# pc_kalam_gpio_cap.net
KiCad netlist of a schematic drawn in EAGLE
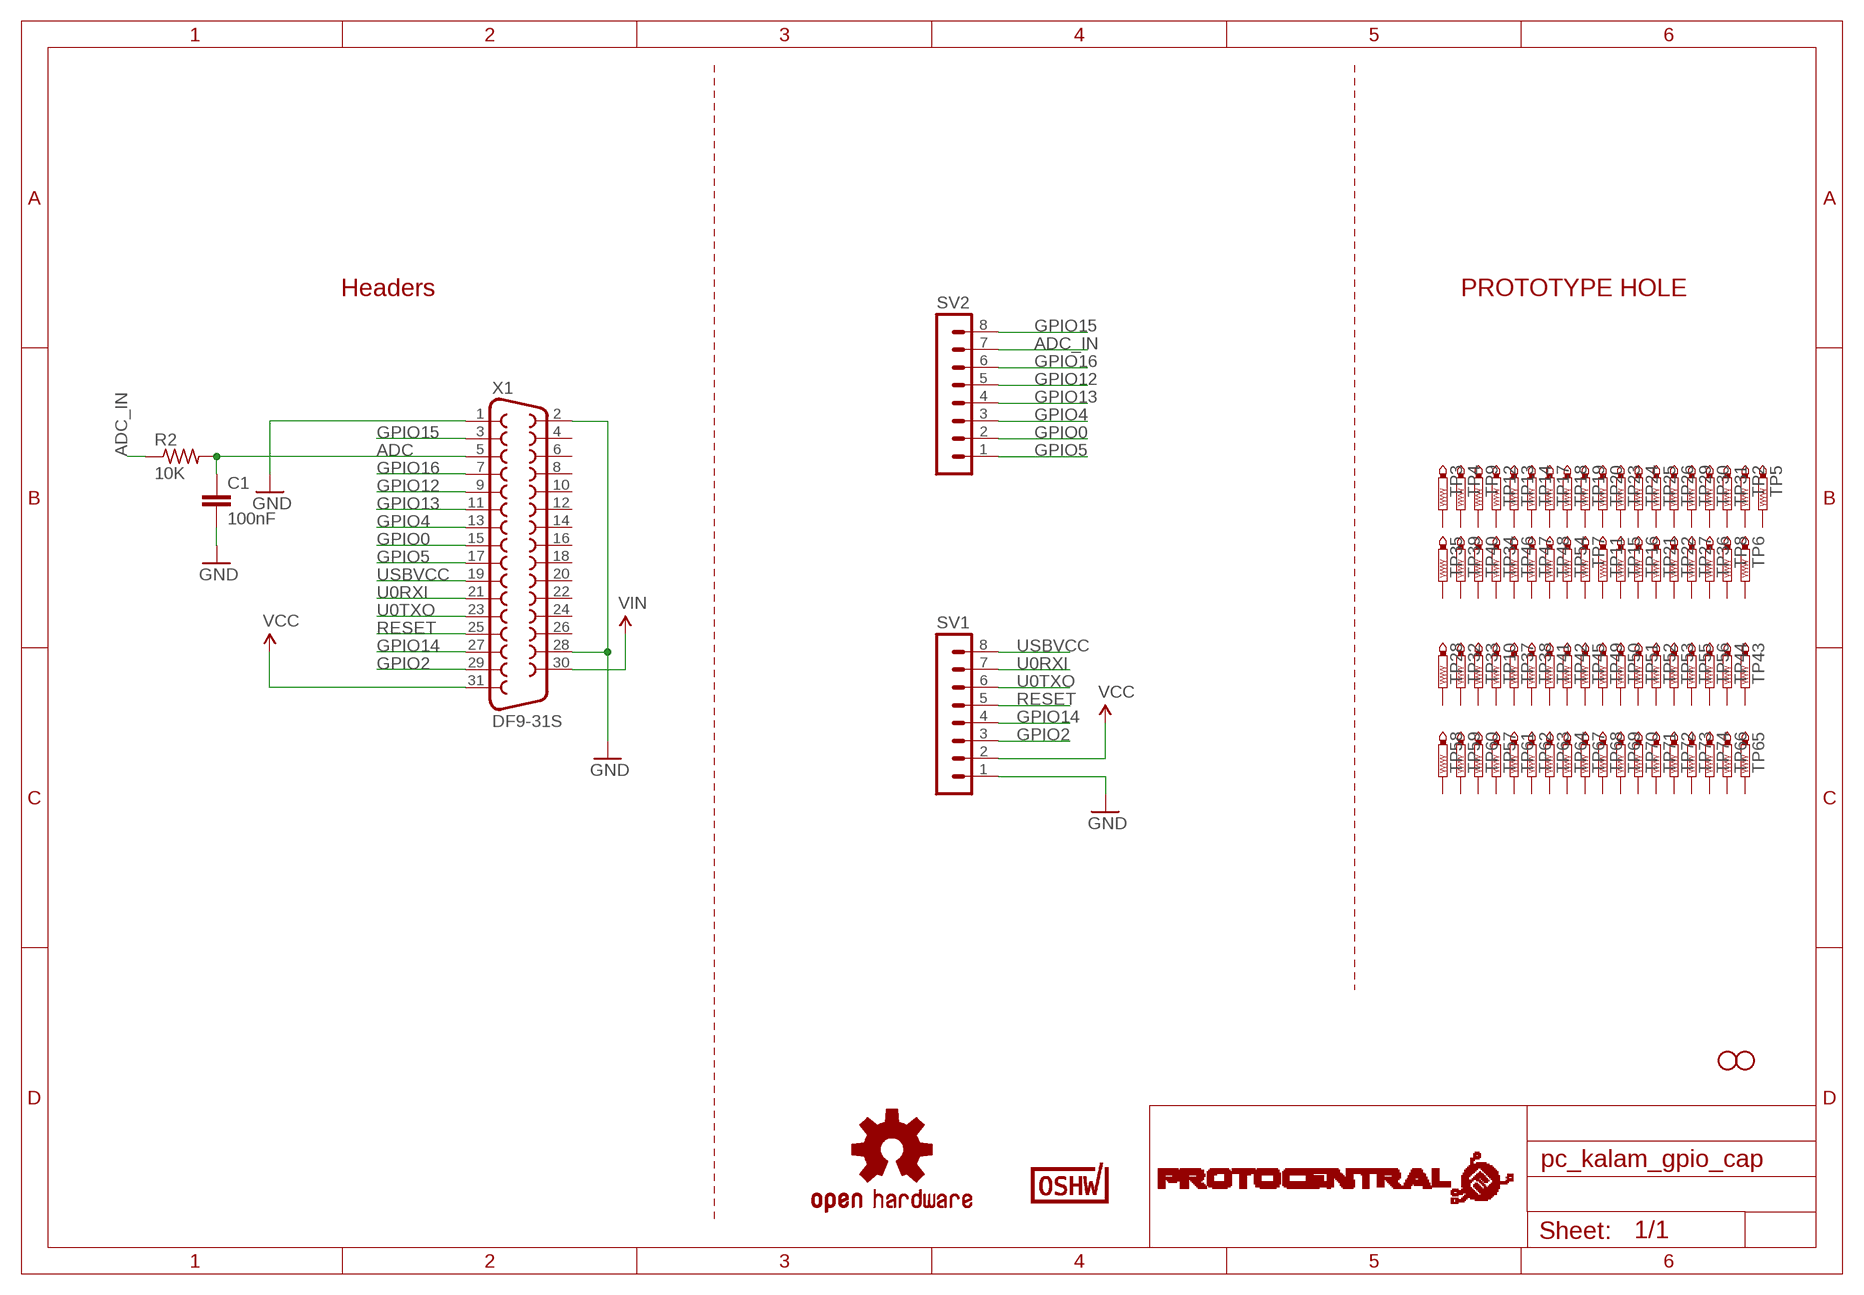
[diagram p0: schematic, sheet 1]

(export (version "E")
  (design (tool "Eeschema 10.0.6"))
  (components
    (comp (ref "C1")
      (value "100nF")
      (footprint "eagle-import:C0805")
      (libsource (lib "eagle-import") (part "C-EUC0805"))
    )
    (comp (ref "R2")
      (value "10K")
      (footprint "eagle-import:R0805")
      (libsource (lib "eagle-import") (part "R-US_R0805"))
    )
    (comp (ref "STANDOFF7")
      (value "STAND-OFF")
      (footprint "eagle-import:STAND-OFF")
      (libsource (lib "eagle-import") (part "STAND-OFF"))
    )
    (comp (ref "STANDOFF8")
      (value "STAND-OFF")
      (footprint "eagle-import:STAND-OFF")
      (libsource (lib "eagle-import") (part "STAND-OFF"))
    )
    (comp (ref "SV1")
      (value "MA08-1")
      (footprint "eagle-import:MA08-1")
      (libsource (lib "eagle-import") (part "MA08-1"))
    )
    (comp (ref "SV2")
      (value "MA08-1")
      (footprint "eagle-import:MA08-1")
      (libsource (lib "eagle-import") (part "MA08-1"))
    )
    (comp (ref "TP2")
      (value "PTR1PAD1-13")
      (footprint "eagle-import:P1-13")
      (libsource (lib "eagle-import") (part "PTR1PAD1-13"))
    )
    (comp (ref "TP3")
      (value "PTR1PAD1-13")
      (footprint "eagle-import:P1-13")
      (libsource (lib "eagle-import") (part "PTR1PAD1-13"))
    )
    (comp (ref "TP4")
      (value "PTR1PAD1-13")
      (footprint "eagle-import:P1-13")
      (libsource (lib "eagle-import") (part "PTR1PAD1-13"))
    )
    (comp (ref "TP5")
      (value "PTR1PAD1-13")
      (footprint "eagle-import:P1-13")
      (libsource (lib "eagle-import") (part "PTR1PAD1-13"))
    )
    (comp (ref "TP6")
      (value "PTR1PAD1-13")
      (footprint "eagle-import:P1-13")
      (libsource (lib "eagle-import") (part "PTR1PAD1-13"))
    )
    (comp (ref "TP7")
      (value "PTR1PAD1-13")
      (footprint "eagle-import:P1-13")
      (libsource (lib "eagle-import") (part "PTR1PAD1-13"))
    )
    (comp (ref "TP8")
      (value "PTR1PAD1-13")
      (footprint "eagle-import:P1-13")
      (libsource (lib "eagle-import") (part "PTR1PAD1-13"))
    )
    (comp (ref "TP9")
      (value "PTR1PAD1-13")
      (footprint "eagle-import:P1-13")
      (libsource (lib "eagle-import") (part "PTR1PAD1-13"))
    )
    (comp (ref "TP10")
      (value "PTR1PAD1-13")
      (footprint "eagle-import:P1-13")
      (libsource (lib "eagle-import") (part "PTR1PAD1-13"))
    )
    (comp (ref "TP11")
      (value "PTR1PAD1-13")
      (footprint "eagle-import:P1-13")
      (libsource (lib "eagle-import") (part "PTR1PAD1-13"))
    )
    (comp (ref "TP12")
      (value "PTR1PAD1-13")
      (footprint "eagle-import:P1-13")
      (libsource (lib "eagle-import") (part "PTR1PAD1-13"))
    )
    (comp (ref "TP13")
      (value "PTR1PAD1-13")
      (footprint "eagle-import:P1-13")
      (libsource (lib "eagle-import") (part "PTR1PAD1-13"))
    )
    (comp (ref "TP14")
      (value "PTR1PAD1-13")
      (footprint "eagle-import:P1-13")
      (libsource (lib "eagle-import") (part "PTR1PAD1-13"))
    )
    (comp (ref "TP15")
      (value "PTR1PAD1-13")
      (footprint "eagle-import:P1-13")
      (libsource (lib "eagle-import") (part "PTR1PAD1-13"))
    )
    (comp (ref "TP16")
      (value "PTR1PAD1-13")
      (footprint "eagle-import:P1-13")
      (libsource (lib "eagle-import") (part "PTR1PAD1-13"))
    )
    (comp (ref "TP17")
      (value "PTR1PAD1-13")
      (footprint "eagle-import:P1-13")
      (libsource (lib "eagle-import") (part "PTR1PAD1-13"))
    )
    (comp (ref "TP18")
      (value "PTR1PAD1-13")
      (footprint "eagle-import:P1-13")
      (libsource (lib "eagle-import") (part "PTR1PAD1-13"))
    )
    (comp (ref "TP19")
      (value "PTR1PAD1-13")
      (footprint "eagle-import:P1-13")
      (libsource (lib "eagle-import") (part "PTR1PAD1-13"))
    )
    (comp (ref "TP20")
      (value "PTR1PAD1-13")
      (footprint "eagle-import:P1-13")
      (libsource (lib "eagle-import") (part "PTR1PAD1-13"))
    )
    (comp (ref "TP21")
      (value "PTR1PAD1-13")
      (footprint "eagle-import:P1-13")
      (libsource (lib "eagle-import") (part "PTR1PAD1-13"))
    )
    (comp (ref "TP22")
      (value "PTR1PAD1-13")
      (footprint "eagle-import:P1-13")
      (libsource (lib "eagle-import") (part "PTR1PAD1-13"))
    )
    (comp (ref "TP23")
      (value "PTR1PAD1-13")
      (footprint "eagle-import:P1-13")
      (libsource (lib "eagle-import") (part "PTR1PAD1-13"))
    )
    (comp (ref "TP24")
      (value "PTR1PAD1-13")
      (footprint "eagle-import:P1-13")
      (libsource (lib "eagle-import") (part "PTR1PAD1-13"))
    )
    (comp (ref "TP25")
      (value "PTR1PAD1-13")
      (footprint "eagle-import:P1-13")
      (libsource (lib "eagle-import") (part "PTR1PAD1-13"))
    )
    (comp (ref "TP26")
      (value "PTR1PAD1-13")
      (footprint "eagle-import:P1-13")
      (libsource (lib "eagle-import") (part "PTR1PAD1-13"))
    )
    (comp (ref "TP27")
      (value "PTR1PAD1-13")
      (footprint "eagle-import:P1-13")
      (libsource (lib "eagle-import") (part "PTR1PAD1-13"))
    )
    (comp (ref "TP28")
      (value "PTR1PAD1-13")
      (footprint "eagle-import:P1-13")
      (libsource (lib "eagle-import") (part "PTR1PAD1-13"))
    )
    (comp (ref "TP29")
      (value "PTR1PAD1-13")
      (footprint "eagle-import:P1-13")
      (libsource (lib "eagle-import") (part "PTR1PAD1-13"))
    )
    (comp (ref "TP30")
      (value "PTR1PAD1-13")
      (footprint "eagle-import:P1-13")
      (libsource (lib "eagle-import") (part "PTR1PAD1-13"))
    )
    (comp (ref "TP31")
      (value "PTR1PAD1-13")
      (footprint "eagle-import:P1-13")
      (libsource (lib "eagle-import") (part "PTR1PAD1-13"))
    )
    (comp (ref "TP32")
      (value "PTR1PAD1-13")
      (footprint "eagle-import:P1-13")
      (libsource (lib "eagle-import") (part "PTR1PAD1-13"))
    )
    (comp (ref "TP33")
      (value "PTR1PAD1-13")
      (footprint "eagle-import:P1-13")
      (libsource (lib "eagle-import") (part "PTR1PAD1-13"))
    )
    (comp (ref "TP34")
      (value "PTR1PAD1-13")
      (footprint "eagle-import:P1-13")
      (libsource (lib "eagle-import") (part "PTR1PAD1-13"))
    )
    (comp (ref "TP35")
      (value "PTR1PAD1-13")
      (footprint "eagle-import:P1-13")
      (libsource (lib "eagle-import") (part "PTR1PAD1-13"))
    )
    (comp (ref "TP36")
      (value "PTR1PAD1-13")
      (footprint "eagle-import:P1-13")
      (libsource (lib "eagle-import") (part "PTR1PAD1-13"))
    )
    (comp (ref "TP37")
      (value "PTR1PAD1-13")
      (footprint "eagle-import:P1-13")
      (libsource (lib "eagle-import") (part "PTR1PAD1-13"))
    )
    (comp (ref "TP38")
      (value "PTR1PAD1-13")
      (footprint "eagle-import:P1-13")
      (libsource (lib "eagle-import") (part "PTR1PAD1-13"))
    )
    (comp (ref "TP39")
      (value "PTR1PAD1-13")
      (footprint "eagle-import:P1-13")
      (libsource (lib "eagle-import") (part "PTR1PAD1-13"))
    )
    (comp (ref "TP40")
      (value "PTR1PAD1-13")
      (footprint "eagle-import:P1-13")
      (libsource (lib "eagle-import") (part "PTR1PAD1-13"))
    )
    (comp (ref "TP41")
      (value "PTR1PAD1-13")
      (footprint "eagle-import:P1-13")
      (libsource (lib "eagle-import") (part "PTR1PAD1-13"))
    )
    (comp (ref "TP42")
      (value "PTR1PAD1-13")
      (footprint "eagle-import:P1-13")
      (libsource (lib "eagle-import") (part "PTR1PAD1-13"))
    )
    (comp (ref "TP43")
      (value "PTR1PAD1-13")
      (footprint "eagle-import:P1-13")
      (libsource (lib "eagle-import") (part "PTR1PAD1-13"))
    )
    (comp (ref "TP44")
      (value "PTR1PAD1-13")
      (footprint "eagle-import:P1-13")
      (libsource (lib "eagle-import") (part "PTR1PAD1-13"))
    )
    (comp (ref "TP45")
      (value "PTR1PAD1-13")
      (footprint "eagle-import:P1-13")
      (libsource (lib "eagle-import") (part "PTR1PAD1-13"))
    )
    (comp (ref "TP46")
      (value "PTR1PAD1-13")
      (footprint "eagle-import:P1-13")
      (libsource (lib "eagle-import") (part "PTR1PAD1-13"))
    )
    (comp (ref "TP47")
      (value "PTR1PAD1-13")
      (footprint "eagle-import:P1-13")
      (libsource (lib "eagle-import") (part "PTR1PAD1-13"))
    )
    (comp (ref "TP48")
      (value "PTR1PAD1-13")
      (footprint "eagle-import:P1-13")
      (libsource (lib "eagle-import") (part "PTR1PAD1-13"))
    )
    (comp (ref "TP49")
      (value "PTR1PAD1-13")
      (footprint "eagle-import:P1-13")
      (libsource (lib "eagle-import") (part "PTR1PAD1-13"))
    )
    (comp (ref "TP50")
      (value "PTR1PAD1-13")
      (footprint "eagle-import:P1-13")
      (libsource (lib "eagle-import") (part "PTR1PAD1-13"))
    )
    (comp (ref "TP51")
      (value "PTR1PAD1-13")
      (footprint "eagle-import:P1-13")
      (libsource (lib "eagle-import") (part "PTR1PAD1-13"))
    )
    (comp (ref "TP52")
      (value "PTR1PAD1-13")
      (footprint "eagle-import:P1-13")
      (libsource (lib "eagle-import") (part "PTR1PAD1-13"))
    )
    (comp (ref "TP53")
      (value "PTR1PAD1-13")
      (footprint "eagle-import:P1-13")
      (libsource (lib "eagle-import") (part "PTR1PAD1-13"))
    )
    (comp (ref "TP54")
      (value "PTR1PAD1-13")
      (footprint "eagle-import:P1-13")
      (libsource (lib "eagle-import") (part "PTR1PAD1-13"))
    )
    (comp (ref "TP55")
      (value "PTR1PAD1-13")
      (footprint "eagle-import:P1-13")
      (libsource (lib "eagle-import") (part "PTR1PAD1-13"))
    )
    (comp (ref "TP56")
      (value "PTR1PAD1-13")
      (footprint "eagle-import:P1-13")
      (libsource (lib "eagle-import") (part "PTR1PAD1-13"))
    )
    (comp (ref "TP57")
      (value "PTR1PAD1-13")
      (footprint "eagle-import:P1-13")
      (libsource (lib "eagle-import") (part "PTR1PAD1-13"))
    )
    (comp (ref "TP58")
      (value "PTR1PAD1-13")
      (footprint "eagle-import:P1-13")
      (libsource (lib "eagle-import") (part "PTR1PAD1-13"))
    )
    (comp (ref "TP59")
      (value "PTR1PAD1-13")
      (footprint "eagle-import:P1-13")
      (libsource (lib "eagle-import") (part "PTR1PAD1-13"))
    )
    (comp (ref "TP60")
      (value "PTR1PAD1-13")
      (footprint "eagle-import:P1-13")
      (libsource (lib "eagle-import") (part "PTR1PAD1-13"))
    )
    (comp (ref "TP61")
      (value "PTR1PAD1-13")
      (footprint "eagle-import:P1-13")
      (libsource (lib "eagle-import") (part "PTR1PAD1-13"))
    )
    (comp (ref "TP62")
      (value "PTR1PAD1-13")
      (footprint "eagle-import:P1-13")
      (libsource (lib "eagle-import") (part "PTR1PAD1-13"))
    )
    (comp (ref "TP63")
      (value "PTR1PAD1-13")
      (footprint "eagle-import:P1-13")
      (libsource (lib "eagle-import") (part "PTR1PAD1-13"))
    )
    (comp (ref "TP64")
      (value "PTR1PAD1-13")
      (footprint "eagle-import:P1-13")
      (libsource (lib "eagle-import") (part "PTR1PAD1-13"))
    )
    (comp (ref "TP65")
      (value "PTR1PAD1-13")
      (footprint "eagle-import:P1-13")
      (libsource (lib "eagle-import") (part "PTR1PAD1-13"))
    )
    (comp (ref "TP66")
      (value "PTR1PAD1-13")
      (footprint "eagle-import:P1-13")
      (libsource (lib "eagle-import") (part "PTR1PAD1-13"))
    )
    (comp (ref "TP67")
      (value "PTR1PAD1-13")
      (footprint "eagle-import:P1-13")
      (libsource (lib "eagle-import") (part "PTR1PAD1-13"))
    )
    (comp (ref "TP68")
      (value "PTR1PAD1-13")
      (footprint "eagle-import:P1-13")
      (libsource (lib "eagle-import") (part "PTR1PAD1-13"))
    )
    (comp (ref "TP69")
      (value "PTR1PAD1-13")
      (footprint "eagle-import:P1-13")
      (libsource (lib "eagle-import") (part "PTR1PAD1-13"))
    )
    (comp (ref "TP70")
      (value "PTR1PAD1-13")
      (footprint "eagle-import:P1-13")
      (libsource (lib "eagle-import") (part "PTR1PAD1-13"))
    )
    (comp (ref "TP71")
      (value "PTR1PAD1-13")
      (footprint "eagle-import:P1-13")
      (libsource (lib "eagle-import") (part "PTR1PAD1-13"))
    )
    (comp (ref "TP72")
      (value "PTR1PAD1-13")
      (footprint "eagle-import:P1-13")
      (libsource (lib "eagle-import") (part "PTR1PAD1-13"))
    )
    (comp (ref "TP73")
      (value "PTR1PAD1-13")
      (footprint "eagle-import:P1-13")
      (libsource (lib "eagle-import") (part "PTR1PAD1-13"))
    )
    (comp (ref "TP74")
      (value "PTR1PAD1-13")
      (footprint "eagle-import:P1-13")
      (libsource (lib "eagle-import") (part "PTR1PAD1-13"))
    )
    (comp (ref "U$2")
      (value "CERT-SMALL")
      (footprint "eagle-import:CERT-SMALL-SILK")
      (libsource (lib "eagle-import") (part "CERT-SMALL"))
    )
    (comp (ref "U$3")
      (value "OSHW-LOGOS")
      (footprint "eagle-import:OSHW-LOGO-S")
      (libsource (lib "eagle-import") (part "OSHW-LOGOS"))
    )
    (comp (ref "U$6")
      (value "PROTY_LOGO_WITH_TEXT")
      (footprint "eagle-import:PROTY_WITH_TEXT")
      (libsource (lib "eagle-import") (part "PROTY_LOGO_WITH_TEXT"))
    )
    (comp (ref "X1")
      (value "DF9-31S")
      (footprint "eagle-import:DF9-31S")
      (fields (field (name "MPN") "DF9-31S-1V(32)"))
      (libsource (lib "eagle-import") (part "DF9-31S"))
    )
  )
  (nets
    (net (code "1") (name "/ADC") (class "Default")
      (node (ref "C1") (pin "1") (pinfunction "1_1") (pintype "passive"))
      (node (ref "R2") (pin "2") (pinfunction "2_2") (pintype "passive"))
      (node (ref "X1") (pin "5") (pinfunction "5_5") (pintype "passive"))
    )
    (net (code "2") (name "/ADC_IN") (class "Default")
      (node (ref "R2") (pin "1") (pinfunction "1_1") (pintype "passive"))
      (node (ref "SV2") (pin "7") (pinfunction "7_7") (pintype "passive"))
    )
    (net (code "3") (name "/GPIO0") (class "Default")
      (node (ref "SV2") (pin "2") (pinfunction "2_2") (pintype "passive"))
      (node (ref "X1") (pin "15") (pinfunction "15_15") (pintype "passive"))
    )
    (net (code "4") (name "/GPIO2") (class "Default")
      (node (ref "SV1") (pin "3") (pinfunction "3_3") (pintype "passive"))
      (node (ref "X1") (pin "29") (pinfunction "29_29") (pintype "passive"))
    )
    (net (code "5") (name "/GPIO4") (class "Default")
      (node (ref "SV2") (pin "3") (pinfunction "3_3") (pintype "passive"))
      (node (ref "X1") (pin "13") (pinfunction "13_13") (pintype "passive"))
    )
    (net (code "6") (name "/GPIO5") (class "Default")
      (node (ref "SV2") (pin "1") (pinfunction "1_1") (pintype "passive"))
      (node (ref "X1") (pin "17") (pinfunction "17_17") (pintype "passive"))
    )
    (net (code "7") (name "/GPIO12") (class "Default")
      (node (ref "SV2") (pin "5") (pinfunction "5_5") (pintype "passive"))
      (node (ref "X1") (pin "9") (pinfunction "9_9") (pintype "passive"))
    )
    (net (code "8") (name "/GPIO13") (class "Default")
      (node (ref "SV2") (pin "4") (pinfunction "4_4") (pintype "passive"))
      (node (ref "X1") (pin "11") (pinfunction "11_11") (pintype "passive"))
    )
    (net (code "9") (name "/GPIO14") (class "Default")
      (node (ref "SV1") (pin "4") (pinfunction "4_4") (pintype "passive"))
      (node (ref "X1") (pin "27") (pinfunction "27_27") (pintype "passive"))
    )
    (net (code "10") (name "/GPIO15") (class "Default")
      (node (ref "SV2") (pin "8") (pinfunction "8_8") (pintype "passive"))
      (node (ref "X1") (pin "3") (pinfunction "3_3") (pintype "passive"))
    )
    (net (code "11") (name "/GPIO16") (class "Default")
      (node (ref "SV2") (pin "6") (pinfunction "6_6") (pintype "passive"))
      (node (ref "X1") (pin "7") (pinfunction "7_7") (pintype "passive"))
    )
    (net (code "12") (name "/RESET") (class "Default")
      (node (ref "SV1") (pin "5") (pinfunction "5_5") (pintype "passive"))
      (node (ref "X1") (pin "25") (pinfunction "25_25") (pintype "passive"))
    )
    (net (code "13") (name "/U0RXI") (class "Default")
      (node (ref "SV1") (pin "7") (pinfunction "7_7") (pintype "passive"))
      (node (ref "X1") (pin "21") (pinfunction "21_21") (pintype "passive"))
    )
    (net (code "14") (name "/U0TXO") (class "Default")
      (node (ref "SV1") (pin "6") (pinfunction "6_6") (pintype "passive"))
      (node (ref "X1") (pin "23") (pinfunction "23_23") (pintype "passive"))
    )
    (net (code "15") (name "/USBVCC") (class "Default")
      (node (ref "SV1") (pin "8") (pinfunction "8_8") (pintype "passive"))
      (node (ref "X1") (pin "19") (pinfunction "19_19") (pintype "passive"))
    )
    (net (code "16") (name "GND") (class "Default")
      (node (ref "C1") (pin "2") (pinfunction "2_2") (pintype "passive"))
      (node (ref "SV1") (pin "1") (pinfunction "1_1") (pintype "passive"))
      (node (ref "X1") (pin "1") (pinfunction "1_1") (pintype "passive"))
      (node (ref "X1") (pin "2") (pinfunction "2_2") (pintype "passive"))
      (node (ref "X1") (pin "28") (pinfunction "28_28") (pintype "passive"))
    )
    (net (code "17") (name "VCC") (class "Default")
      (node (ref "SV1") (pin "2") (pinfunction "2_2") (pintype "passive"))
      (node (ref "X1") (pin "31") (pinfunction "31_31") (pintype "passive"))
    )
    (net (code "18") (name "VIN") (class "Default")
      (node (ref "X1") (pin "30") (pinfunction "30_30") (pintype "passive"))
    )
    (net (code "19") (name "unconnected-(TP2-PadTP)") (class "Default")
      (node (ref "TP2") (pin "TP") (pinfunction "TP_TP") (pintype "input"))
    )
    (net (code "20") (name "unconnected-(TP3-PadTP)") (class "Default")
      (node (ref "TP3") (pin "TP") (pinfunction "TP_TP") (pintype "input"))
    )
    (net (code "21") (name "unconnected-(TP4-PadTP)") (class "Default")
      (node (ref "TP4") (pin "TP") (pinfunction "TP_TP") (pintype "input"))
    )
    (net (code "22") (name "unconnected-(TP5-PadTP)") (class "Default")
      (node (ref "TP5") (pin "TP") (pinfunction "TP_TP") (pintype "input"))
    )
    (net (code "23") (name "unconnected-(TP6-PadTP)") (class "Default")
      (node (ref "TP6") (pin "TP") (pinfunction "TP_TP") (pintype "input"))
    )
    (net (code "24") (name "unconnected-(TP7-PadTP)") (class "Default")
      (node (ref "TP7") (pin "TP") (pinfunction "TP_TP") (pintype "input"))
    )
    (net (code "25") (name "unconnected-(TP8-PadTP)") (class "Default")
      (node (ref "TP8") (pin "TP") (pinfunction "TP_TP") (pintype "input"))
    )
    (net (code "26") (name "unconnected-(TP9-PadTP)") (class "Default")
      (node (ref "TP9") (pin "TP") (pinfunction "TP_TP") (pintype "input"))
    )
    (net (code "27") (name "unconnected-(TP10-PadTP)") (class "Default")
      (node (ref "TP10") (pin "TP") (pinfunction "TP_TP") (pintype "input"))
    )
    (net (code "28") (name "unconnected-(TP11-PadTP)") (class "Default")
      (node (ref "TP11") (pin "TP") (pinfunction "TP_TP") (pintype "input"))
    )
    (net (code "29") (name "unconnected-(TP12-PadTP)") (class "Default")
      (node (ref "TP12") (pin "TP") (pinfunction "TP_TP") (pintype "input"))
    )
    (net (code "30") (name "unconnected-(TP13-PadTP)") (class "Default")
      (node (ref "TP13") (pin "TP") (pinfunction "TP_TP") (pintype "input"))
    )
    (net (code "31") (name "unconnected-(TP14-PadTP)") (class "Default")
      (node (ref "TP14") (pin "TP") (pinfunction "TP_TP") (pintype "input"))
    )
    (net (code "32") (name "unconnected-(TP15-PadTP)") (class "Default")
      (node (ref "TP15") (pin "TP") (pinfunction "TP_TP") (pintype "input"))
    )
    (net (code "33") (name "unconnected-(TP16-PadTP)") (class "Default")
      (node (ref "TP16") (pin "TP") (pinfunction "TP_TP") (pintype "input"))
    )
    (net (code "34") (name "unconnected-(TP17-PadTP)") (class "Default")
      (node (ref "TP17") (pin "TP") (pinfunction "TP_TP") (pintype "input"))
    )
    (net (code "35") (name "unconnected-(TP18-PadTP)") (class "Default")
      (node (ref "TP18") (pin "TP") (pinfunction "TP_TP") (pintype "input"))
    )
    (net (code "36") (name "unconnected-(TP19-PadTP)") (class "Default")
      (node (ref "TP19") (pin "TP") (pinfunction "TP_TP") (pintype "input"))
    )
    (net (code "37") (name "unconnected-(TP20-PadTP)") (class "Default")
      (node (ref "TP20") (pin "TP") (pinfunction "TP_TP") (pintype "input"))
    )
    (net (code "38") (name "unconnected-(TP21-PadTP)") (class "Default")
      (node (ref "TP21") (pin "TP") (pinfunction "TP_TP") (pintype "input"))
    )
    (net (code "39") (name "unconnected-(TP22-PadTP)") (class "Default")
      (node (ref "TP22") (pin "TP") (pinfunction "TP_TP") (pintype "input"))
    )
    (net (code "40") (name "unconnected-(TP23-PadTP)") (class "Default")
      (node (ref "TP23") (pin "TP") (pinfunction "TP_TP") (pintype "input"))
    )
    (net (code "41") (name "unconnected-(TP24-PadTP)") (class "Default")
      (node (ref "TP24") (pin "TP") (pinfunction "TP_TP") (pintype "input"))
    )
    (net (code "42") (name "unconnected-(TP25-PadTP)") (class "Default")
      (node (ref "TP25") (pin "TP") (pinfunction "TP_TP") (pintype "input"))
    )
    (net (code "43") (name "unconnected-(TP26-PadTP)") (class "Default")
      (node (ref "TP26") (pin "TP") (pinfunction "TP_TP") (pintype "input"))
    )
    (net (code "44") (name "unconnected-(TP27-PadTP)") (class "Default")
      (node (ref "TP27") (pin "TP") (pinfunction "TP_TP") (pintype "input"))
    )
    (net (code "45") (name "unconnected-(TP28-PadTP)") (class "Default")
      (node (ref "TP28") (pin "TP") (pinfunction "TP_TP") (pintype "input"))
    )
    (net (code "46") (name "unconnected-(TP29-PadTP)") (class "Default")
      (node (ref "TP29") (pin "TP") (pinfunction "TP_TP") (pintype "input"))
    )
    (net (code "47") (name "unconnected-(TP30-PadTP)") (class "Default")
      (node (ref "TP30") (pin "TP") (pinfunction "TP_TP") (pintype "input"))
    )
    (net (code "48") (name "unconnected-(TP31-PadTP)") (class "Default")
      (node (ref "TP31") (pin "TP") (pinfunction "TP_TP") (pintype "input"))
    )
    (net (code "49") (name "unconnected-(TP32-PadTP)") (class "Default")
      (node (ref "TP32") (pin "TP") (pinfunction "TP_TP") (pintype "input"))
    )
    (net (code "50") (name "unconnected-(TP33-PadTP)") (class "Default")
      (node (ref "TP33") (pin "TP") (pinfunction "TP_TP") (pintype "input"))
    )
    (net (code "51") (name "unconnected-(TP34-PadTP)") (class "Default")
      (node (ref "TP34") (pin "TP") (pinfunction "TP_TP") (pintype "input"))
    )
    (net (code "52") (name "unconnected-(TP35-PadTP)") (class "Default")
      (node (ref "TP35") (pin "TP") (pinfunction "TP_TP") (pintype "input"))
    )
    (net (code "53") (name "unconnected-(TP36-PadTP)") (class "Default")
      (node (ref "TP36") (pin "TP") (pinfunction "TP_TP") (pintype "input"))
    )
    (net (code "54") (name "unconnected-(TP37-PadTP)") (class "Default")
      (node (ref "TP37") (pin "TP") (pinfunction "TP_TP") (pintype "input"))
    )
    (net (code "55") (name "unconnected-(TP38-PadTP)") (class "Default")
      (node (ref "TP38") (pin "TP") (pinfunction "TP_TP") (pintype "input"))
    )
    (net (code "56") (name "unconnected-(TP39-PadTP)") (class "Default")
      (node (ref "TP39") (pin "TP") (pinfunction "TP_TP") (pintype "input"))
    )
    (net (code "57") (name "unconnected-(TP40-PadTP)") (class "Default")
      (node (ref "TP40") (pin "TP") (pinfunction "TP_TP") (pintype "input"))
    )
    (net (code "58") (name "unconnected-(TP41-PadTP)") (class "Default")
      (node (ref "TP41") (pin "TP") (pinfunction "TP_TP") (pintype "input"))
    )
    (net (code "59") (name "unconnected-(TP42-PadTP)") (class "Default")
      (node (ref "TP42") (pin "TP") (pinfunction "TP_TP") (pintype "input"))
    )
    (net (code "60") (name "unconnected-(TP43-PadTP)") (class "Default")
      (node (ref "TP43") (pin "TP") (pinfunction "TP_TP") (pintype "input"))
    )
    (net (code "61") (name "unconnected-(TP44-PadTP)") (class "Default")
      (node (ref "TP44") (pin "TP") (pinfunction "TP_TP") (pintype "input"))
    )
    (net (code "62") (name "unconnected-(TP45-PadTP)") (class "Default")
      (node (ref "TP45") (pin "TP") (pinfunction "TP_TP") (pintype "input"))
    )
    (net (code "63") (name "unconnected-(TP46-PadTP)") (class "Default")
      (node (ref "TP46") (pin "TP") (pinfunction "TP_TP") (pintype "input"))
    )
    (net (code "64") (name "unconnected-(TP47-PadTP)") (class "Default")
      (node (ref "TP47") (pin "TP") (pinfunction "TP_TP") (pintype "input"))
    )
    (net (code "65") (name "unconnected-(TP48-PadTP)") (class "Default")
      (node (ref "TP48") (pin "TP") (pinfunction "TP_TP") (pintype "input"))
    )
    (net (code "66") (name "unconnected-(TP49-PadTP)") (class "Default")
      (node (ref "TP49") (pin "TP") (pinfunction "TP_TP") (pintype "input"))
    )
    (net (code "67") (name "unconnected-(TP50-PadTP)") (class "Default")
      (node (ref "TP50") (pin "TP") (pinfunction "TP_TP") (pintype "input"))
    )
    (net (code "68") (name "unconnected-(TP51-PadTP)") (class "Default")
      (node (ref "TP51") (pin "TP") (pinfunction "TP_TP") (pintype "input"))
    )
    (net (code "69") (name "unconnected-(TP52-PadTP)") (class "Default")
      (node (ref "TP52") (pin "TP") (pinfunction "TP_TP") (pintype "input"))
    )
    (net (code "70") (name "unconnected-(TP53-PadTP)") (class "Default")
      (node (ref "TP53") (pin "TP") (pinfunction "TP_TP") (pintype "input"))
    )
    (net (code "71") (name "unconnected-(TP54-PadTP)") (class "Default")
      (node (ref "TP54") (pin "TP") (pinfunction "TP_TP") (pintype "input"))
    )
    (net (code "72") (name "unconnected-(TP55-PadTP)") (class "Default")
      (node (ref "TP55") (pin "TP") (pinfunction "TP_TP") (pintype "input"))
    )
    (net (code "73") (name "unconnected-(TP56-PadTP)") (class "Default")
      (node (ref "TP56") (pin "TP") (pinfunction "TP_TP") (pintype "input"))
    )
    (net (code "74") (name "unconnected-(TP57-PadTP)") (class "Default")
      (node (ref "TP57") (pin "TP") (pinfunction "TP_TP") (pintype "input"))
    )
    (net (code "75") (name "unconnected-(TP58-PadTP)") (class "Default")
      (node (ref "TP58") (pin "TP") (pinfunction "TP_TP") (pintype "input"))
    )
    (net (code "76") (name "unconnected-(TP59-PadTP)") (class "Default")
      (node (ref "TP59") (pin "TP") (pinfunction "TP_TP") (pintype "input"))
    )
    (net (code "77") (name "unconnected-(TP60-PadTP)") (class "Default")
      (node (ref "TP60") (pin "TP") (pinfunction "TP_TP") (pintype "input"))
    )
    (net (code "78") (name "unconnected-(TP61-PadTP)") (class "Default")
      (node (ref "TP61") (pin "TP") (pinfunction "TP_TP") (pintype "input"))
    )
    (net (code "79") (name "unconnected-(TP62-PadTP)") (class "Default")
      (node (ref "TP62") (pin "TP") (pinfunction "TP_TP") (pintype "input"))
    )
    (net (code "80") (name "unconnected-(TP63-PadTP)") (class "Default")
      (node (ref "TP63") (pin "TP") (pinfunction "TP_TP") (pintype "input"))
    )
    (net (code "81") (name "unconnected-(TP64-PadTP)") (class "Default")
      (node (ref "TP64") (pin "TP") (pinfunction "TP_TP") (pintype "input"))
    )
    (net (code "82") (name "unconnected-(TP65-PadTP)") (class "Default")
      (node (ref "TP65") (pin "TP") (pinfunction "TP_TP") (pintype "input"))
    )
    (net (code "83") (name "unconnected-(TP66-PadTP)") (class "Default")
      (node (ref "TP66") (pin "TP") (pinfunction "TP_TP") (pintype "input"))
    )
    (net (code "84") (name "unconnected-(TP67-PadTP)") (class "Default")
      (node (ref "TP67") (pin "TP") (pinfunction "TP_TP") (pintype "input"))
    )
    (net (code "85") (name "unconnected-(TP68-PadTP)") (class "Default")
      (node (ref "TP68") (pin "TP") (pinfunction "TP_TP") (pintype "input"))
    )
    (net (code "86") (name "unconnected-(TP69-PadTP)") (class "Default")
      (node (ref "TP69") (pin "TP") (pinfunction "TP_TP") (pintype "input"))
    )
    (net (code "87") (name "unconnected-(TP70-PadTP)") (class "Default")
      (node (ref "TP70") (pin "TP") (pinfunction "TP_TP") (pintype "input"))
    )
    (net (code "88") (name "unconnected-(TP71-PadTP)") (class "Default")
      (node (ref "TP71") (pin "TP") (pinfunction "TP_TP") (pintype "input"))
    )
    (net (code "89") (name "unconnected-(TP72-PadTP)") (class "Default")
      (node (ref "TP72") (pin "TP") (pinfunction "TP_TP") (pintype "input"))
    )
    (net (code "90") (name "unconnected-(TP73-PadTP)") (class "Default")
      (node (ref "TP73") (pin "TP") (pinfunction "TP_TP") (pintype "input"))
    )
    (net (code "91") (name "unconnected-(TP74-PadTP)") (class "Default")
      (node (ref "TP74") (pin "TP") (pinfunction "TP_TP") (pintype "input"))
    )
    (net (code "92") (name "unconnected-(X1-Pad4)") (class "Default")
      (node (ref "X1") (pin "4") (pinfunction "4_4") (pintype "passive"))
    )
    (net (code "93") (name "unconnected-(X1-Pad6)") (class "Default")
      (node (ref "X1") (pin "6") (pinfunction "6_6") (pintype "passive"))
    )
    (net (code "94") (name "unconnected-(X1-Pad8)") (class "Default")
      (node (ref "X1") (pin "8") (pinfunction "8_8") (pintype "passive"))
    )
    (net (code "95") (name "unconnected-(X1-Pad10)") (class "Default")
      (node (ref "X1") (pin "10") (pinfunction "10_10") (pintype "passive"))
    )
    (net (code "96") (name "unconnected-(X1-Pad12)") (class "Default")
      (node (ref "X1") (pin "12") (pinfunction "12_12") (pintype "passive"))
    )
    (net (code "97") (name "unconnected-(X1-Pad14)") (class "Default")
      (node (ref "X1") (pin "14") (pinfunction "14_14") (pintype "passive"))
    )
    (net (code "98") (name "unconnected-(X1-Pad16)") (class "Default")
      (node (ref "X1") (pin "16") (pinfunction "16_16") (pintype "passive"))
    )
    (net (code "99") (name "unconnected-(X1-Pad18)") (class "Default")
      (node (ref "X1") (pin "18") (pinfunction "18_18") (pintype "passive"))
    )
    (net (code "100") (name "unconnected-(X1-Pad20)") (class "Default")
      (node (ref "X1") (pin "20") (pinfunction "20_20") (pintype "passive"))
    )
    (net (code "101") (name "unconnected-(X1-Pad22)") (class "Default")
      (node (ref "X1") (pin "22") (pinfunction "22_22") (pintype "passive"))
    )
    (net (code "102") (name "unconnected-(X1-Pad24)") (class "Default")
      (node (ref "X1") (pin "24") (pinfunction "24_24") (pintype "passive"))
    )
    (net (code "103") (name "unconnected-(X1-Pad26)") (class "Default")
      (node (ref "X1") (pin "26") (pinfunction "26_26") (pintype "passive"))
    )
  )
)
